# ET-UARTPmod.net
KiCad netlist of a schematic drawn in Altium Designer
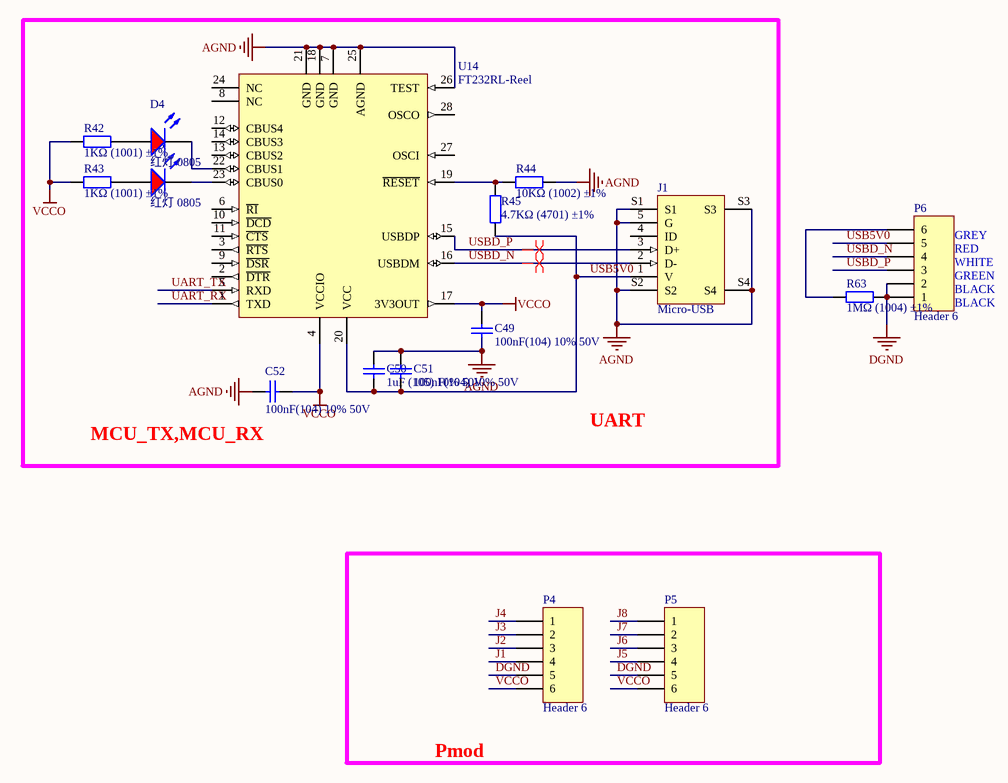
[diagram p0: ET-UARTPmod.SchDoc]

(export (version "E")
  (design (tool "Eeschema 10.0.6"))
  (components
    (comp (ref "C49")
      (value "100nF(104) 10% 50V")
      (footprint "LC-0805_C")
      (description "贴片电容")
      (libsource (lib "Miscellaneous Devices LC") (part "0805 100nF(104) 10% 50V"))
    )
    (comp (ref "C50")
      (value "1uF (105) 10% 50V")
      (footprint "LC-0805_C")
      (description "贴片电容")
      (libsource (lib "Miscellaneous Devices LC") (part "0805 1uF (105) 10% 50V"))
    )
    (comp (ref "C51")
      (value "100nF(104) 10% 50V")
      (footprint "LC-0805_C")
      (description "贴片电容")
      (libsource (lib "Miscellaneous Devices LC") (part "0805 100nF(104) 10% 50V"))
    )
    (comp (ref "C52")
      (value "100nF(104) 10% 50V")
      (footprint "LC-0805_C")
      (description "贴片电容")
      (libsource (lib "Miscellaneous Devices LC") (part "0805 100nF(104) 10% 50V"))
    )
    (comp (ref "D4")
      (value "红灯 0805")
      (footprint "LC-0805_LED_S1")
      (description "发光二极管")
      (libsource (lib "Miscellaneous Devices LC") (part "0805 红灯"))
    )
    (comp (ref "D5")
      (value "红灯 0805")
      (footprint "LC-0805_LED_S1")
      (description "发光二极管")
      (libsource (lib "Miscellaneous Devices LC") (part "0805 红灯"))
    )
    (comp (ref "J1")
      (value "Micro-USB")
      (footprint "USB Micro AB")
      (description "USB 1.1, Right Angle, SMT, A Type, Receptacle, 4 Position, White")
      (fields (field (name "PUBLISHER") "Altium Limited"))
      (libsource (lib "USB Micro AB") (part "Micro-USB"))
    )
    (comp (ref "P4")
      (value "Header 6")
      (footprint "HDR1X6")
      (description "Header, 6-Pin")
      (fields (field (name "PUBLISHER") "Altium Limited"))
      (libsource (lib "Miscellaneous Connectors") (part "Header 6"))
    )
    (comp (ref "P5")
      (value "Header 6")
      (footprint "HDR1X6")
      (description "Header, 6-Pin")
      (fields (field (name "PUBLISHER") "Altium Limited"))
      (libsource (lib "Miscellaneous Connectors") (part "Header 6"))
    )
    (comp (ref "P6")
      (value "Header 6")
      (footprint "HDR1X6")
      (description "Header, 6-Pin")
      (fields (field (name "PUBLISHER") "Altium Limited"))
      (libsource (lib "") (part "Header 6_1"))
    )
    (comp (ref "R42")
      (value "1KΩ (1001) ±1%")
      (footprint "LC-0805_R")
      (description "贴片电阻")
      (libsource (lib "Miscellaneous Devices LC") (part "0805 1KΩ (1001) 1%"))
    )
    (comp (ref "R43")
      (value "1KΩ (1001) ±1%")
      (footprint "LC-0805_R")
      (description "贴片电阻")
      (libsource (lib "Miscellaneous Devices LC") (part "0805 1KΩ (1001) 1%"))
    )
    (comp (ref "R44")
      (value "10KΩ (1002) ±1%")
      (footprint "LC-0805_R")
      (description "贴片电阻")
      (libsource (lib "Miscellaneous Devices LC") (part "0805 10KΩ (1002) 1%"))
    )
    (comp (ref "R45")
      (value "4.7KΩ (4701) ±1%")
      (footprint "LC-0805_R")
      (description "贴片电阻")
      (libsource (lib "Miscellaneous Devices LC") (part "0805 4.7KΩ (4701) 1%"))
    )
    (comp (ref "R63")
      (value "1MΩ (1004) ±1%")
      (footprint "LC-0805_R")
      (description "贴片电阻")
      (libsource (lib "Miscellaneous Devices LC") (part "0805 1MΩ (1004) 1%"))
    )
    (comp (ref "U14")
      (value "FT232RL-Reel")
      (footprint "SSOP-28_N")
      (description "USB UART Asynchronous Serial Data Transfer Chip, SSOP-28, Tape and Reel")
      (fields (field (name "PUBLISHER") "Altium Limited"))
      (libsource (lib "FTDI Communication UART") (part "FT232RL-Reel"))
    )
  )
  (nets
    (net (code "4") (name "/J1") (class "Default")
      (node (ref "P4") (pin "4") (pinfunction "4_4") (pintype "passive"))
    )
    (net (code "5") (name "/J2") (class "Default")
      (node (ref "P4") (pin "3") (pinfunction "3_3") (pintype "passive"))
    )
    (net (code "6") (name "/J3") (class "Default")
      (node (ref "P4") (pin "2") (pinfunction "2_2") (pintype "passive"))
    )
    (net (code "7") (name "/J4") (class "Default")
      (node (ref "P4") (pin "1") (pinfunction "1_1") (pintype "passive"))
    )
    (net (code "8") (name "/J5") (class "Default")
      (node (ref "P5") (pin "4") (pinfunction "4_4") (pintype "passive"))
    )
    (net (code "9") (name "/J6") (class "Default")
      (node (ref "P5") (pin "3") (pinfunction "3_3") (pintype "passive"))
    )
    (net (code "10") (name "/J7") (class "Default")
      (node (ref "P5") (pin "2") (pinfunction "2_2") (pintype "passive"))
    )
    (net (code "11") (name "/J8") (class "Default")
      (node (ref "P5") (pin "1") (pinfunction "1_1") (pintype "passive"))
    )
    (net (code "13") (name "/UART_RX") (class "Default")
      (node (ref "U14") (pin "1") (pinfunction "TXD_1") (pintype "output"))
    )
    (net (code "14") (name "/UART_TX") (class "Default")
      (node (ref "U14") (pin "5") (pinfunction "RXD_5") (pintype "input"))
    )
    (net (code "15") (name "/USB5V0") (class "Default")
      (node (ref "C50") (pin "2") (pinfunction "2_2") (pintype "passive"))
      (node (ref "C51") (pin "2") (pinfunction "2_2") (pintype "passive"))
      (node (ref "J1") (pin "1") (pinfunction "V_1") (pintype "power_in"))
      (node (ref "P6") (pin "5") (pinfunction "5_5") (pintype "passive"))
      (node (ref "R45") (pin "2") (pinfunction "2_2") (pintype "passive"))
      (node (ref "U14") (pin "20") (pinfunction "VCC_20") (pintype "power_in"))
    )
    (net (code "16") (name "/USBD_N") (class "Default")
      (node (ref "J1") (pin "2") (pinfunction "D-_2") (pintype "input"))
      (node (ref "P6") (pin "4") (pinfunction "4_4") (pintype "passive"))
      (node (ref "U14") (pin "16") (pinfunction "USBDM_16") (pintype "bidirectional"))
    )
    (net (code "17") (name "/USBD_P") (class "Default")
      (node (ref "J1") (pin "3") (pinfunction "D+_3") (pintype "input"))
      (node (ref "P6") (pin "3") (pinfunction "3_3") (pintype "passive"))
      (node (ref "U14") (pin "15") (pinfunction "USBDP_15") (pintype "bidirectional"))
    )
    (net (code "19") (name "AGND") (class "Default")
      (node (ref "C49") (pin "2") (pinfunction "2_2") (pintype "passive"))
      (node (ref "C50") (pin "1") (pinfunction "1_1") (pintype "passive"))
      (node (ref "C51") (pin "1") (pinfunction "1_1") (pintype "passive"))
      (node (ref "C52") (pin "1") (pinfunction "1_1") (pintype "passive"))
      (node (ref "J1") (pin "5") (pinfunction "G_5") (pintype "power_in"))
      (node (ref "J1") (pin "S1") (pinfunction "S1_S1") (pintype "power_in"))
      (node (ref "J1") (pin "S2") (pinfunction "S2_S2") (pintype "power_in"))
      (node (ref "J1") (pin "S3") (pinfunction "S3_S3") (pintype "passive"))
      (node (ref "J1") (pin "S4") (pinfunction "S4_S4") (pintype "passive"))
      (node (ref "R44") (pin "1") (pinfunction "1_1") (pintype "passive"))
      (node (ref "U14") (pin "18") (pinfunction "GND_18") (pintype "power_in"))
      (node (ref "U14") (pin "21") (pinfunction "GND_21") (pintype "power_in"))
      (node (ref "U14") (pin "25") (pinfunction "AGND_25") (pintype "power_in"))
      (node (ref "U14") (pin "26") (pinfunction "TEST_26") (pintype "input"))
      (node (ref "U14") (pin "7") (pinfunction "GND_7") (pintype "power_in"))
    )
    (net (code "20") (name "DGND") (class "Default")
      (node (ref "P4") (pin "5") (pinfunction "5_5") (pintype "passive"))
      (node (ref "P5") (pin "5") (pinfunction "5_5") (pintype "passive"))
      (node (ref "P6") (pin "1") (pinfunction "1_1") (pintype "passive"))
      (node (ref "P6") (pin "2") (pinfunction "2_2") (pintype "passive"))
      (node (ref "R63") (pin "2") (pinfunction "2_2") (pintype "passive"))
    )
    (net (code "21") (name "Net-(D4-PadA)") (class "Default")
      (node (ref "D4") (pin "A") (pinfunction "A_A") (pintype "passive"))
      (node (ref "R42") (pin "1") (pinfunction "1_1") (pintype "passive"))
    )
    (net (code "22") (name "Net-(D5-PadA)") (class "Default")
      (node (ref "D5") (pin "A") (pinfunction "A_A") (pintype "passive"))
      (node (ref "R43") (pin "1") (pinfunction "1_1") (pintype "passive"))
    )
    (net (code "23") (name "Net-(P6-Pad6)") (class "Default")
      (node (ref "P6") (pin "6") (pinfunction "6_6") (pintype "passive"))
      (node (ref "R63") (pin "1") (pinfunction "1_1") (pintype "passive"))
    )
    (net (code "24") (name "Net-(U14-CBUS0)") (class "Default")
      (node (ref "D5") (pin "K") (pinfunction "K_K") (pintype "passive"))
      (node (ref "U14") (pin "23") (pinfunction "CBUS0_23") (pintype "bidirectional"))
    )
    (net (code "25") (name "Net-(U14-CBUS1)") (class "Default")
      (node (ref "D4") (pin "K") (pinfunction "K_K") (pintype "passive"))
      (node (ref "U14") (pin "22") (pinfunction "CBUS1_22") (pintype "bidirectional"))
    )
    (net (code "26") (name "Net-(U14-~{RESET})") (class "Default")
      (node (ref "R44") (pin "2") (pinfunction "2_2") (pintype "passive"))
      (node (ref "R45") (pin "1") (pinfunction "1_1") (pintype "passive"))
      (node (ref "U14") (pin "19") (pinfunction "~{RESET}_19") (pintype "input"))
    )
    (net (code "27") (name "VCCO") (class "Default")
      (node (ref "C49") (pin "1") (pinfunction "1_1") (pintype "passive"))
      (node (ref "C52") (pin "2") (pinfunction "2_2") (pintype "passive"))
      (node (ref "P4") (pin "6") (pinfunction "6_6") (pintype "passive"))
      (node (ref "P5") (pin "6") (pinfunction "6_6") (pintype "passive"))
      (node (ref "R42") (pin "2") (pinfunction "2_2") (pintype "passive"))
      (node (ref "R43") (pin "2") (pinfunction "2_2") (pintype "passive"))
      (node (ref "U14") (pin "17") (pinfunction "3V3OUT_17") (pintype "output"))
      (node (ref "U14") (pin "4") (pinfunction "VCCIO_4") (pintype "power_in"))
    )
    (net (code "28") (name "unconnected-(J1-ID-Pad4)") (class "Default")
      (node (ref "J1") (pin "4") (pinfunction "ID_4") (pintype "power_in"))
    )
    (net (code "29") (name "unconnected-(U14-CBUS2-Pad13)") (class "Default")
      (node (ref "U14") (pin "13") (pinfunction "CBUS2_13") (pintype "bidirectional"))
    )
    (net (code "30") (name "unconnected-(U14-CBUS3-Pad14)") (class "Default")
      (node (ref "U14") (pin "14") (pinfunction "CBUS3_14") (pintype "bidirectional"))
    )
    (net (code "31") (name "unconnected-(U14-CBUS4-Pad12)") (class "Default")
      (node (ref "U14") (pin "12") (pinfunction "CBUS4_12") (pintype "bidirectional"))
    )
    (net (code "32") (name "unconnected-(U14-NC-Pad8)") (class "Default")
      (node (ref "U14") (pin "8") (pinfunction "NC_8") (pintype "passive"))
    )
    (net (code "33") (name "unconnected-(U14-NC-Pad24)") (class "Default")
      (node (ref "U14") (pin "24") (pinfunction "NC_24") (pintype "passive"))
    )
    (net (code "34") (name "unconnected-(U14-OSCI-Pad27)") (class "Default")
      (node (ref "U14") (pin "27") (pinfunction "OSCI_27") (pintype "input"))
    )
    (net (code "35") (name "unconnected-(U14-OSCO-Pad28)") (class "Default")
      (node (ref "U14") (pin "28") (pinfunction "OSCO_28") (pintype "output"))
    )
    (net (code "36") (name "unconnected-(U14-~{CTS}-Pad11)") (class "Default")
      (node (ref "U14") (pin "11") (pinfunction "~{CTS}_11") (pintype "input"))
    )
    (net (code "37") (name "unconnected-(U14-~{DCD}-Pad10)") (class "Default")
      (node (ref "U14") (pin "10") (pinfunction "~{DCD}_10") (pintype "input"))
    )
    (net (code "38") (name "unconnected-(U14-~{DSR}-Pad9)") (class "Default")
      (node (ref "U14") (pin "9") (pinfunction "~{DSR}_9") (pintype "input"))
    )
    (net (code "39") (name "unconnected-(U14-~{DTR}-Pad2)") (class "Default")
      (node (ref "U14") (pin "2") (pinfunction "~{DTR}_2") (pintype "output"))
    )
    (net (code "40") (name "unconnected-(U14-~{RI}-Pad6)") (class "Default")
      (node (ref "U14") (pin "6") (pinfunction "~{RI}_6") (pintype "input"))
    )
    (net (code "41") (name "unconnected-(U14-~{RTS}-Pad3)") (class "Default")
      (node (ref "U14") (pin "3") (pinfunction "~{RTS}_3") (pintype "output"))
    )
  )
)
